# oshi-fuse-board-mk-1_1-mini-ato.net
KiCad netlist of a schematic drawn in EAGLE
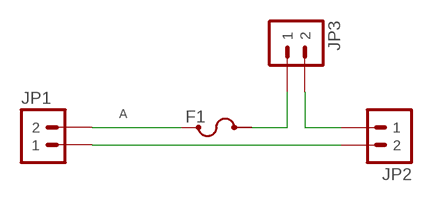
[diagram p0: schematic, sheet 1]

(export (version "E")
  (design (tool "Eeschema 10.0.6"))
  (components
    (comp (ref "F1")
      (value "FUSEMINI-AUTO")
      (footprint "eagle-import:KEYSTONE-MINI-AUTO-FUSE-HOLDER")
      (libsource (lib "eagle-import") (part "FUSEMINI-AUTO"))
    )
    (comp (ref "JP1")
      (value "M025MM")
      (footprint "eagle-import:SCREWTERMINAL-5MM-2")
      (libsource (lib "eagle-import") (part "M025MM"))
    )
    (comp (ref "JP2")
      (value "M025MM")
      (footprint "eagle-import:SCREWTERMINAL-5MM-2")
      (libsource (lib "eagle-import") (part "M025MM"))
    )
    (comp (ref "JP3")
      (value "M025MM")
      (footprint "eagle-import:SCREWTERMINAL-5MM-2")
      (libsource (lib "eagle-import") (part "M025MM"))
    )
  )
  (nets
    (net (code "1") (name "/A") (class "Default")
      (node (ref "F1") (pin "P1@1") (pinfunction "1_P1@1") (pintype "passive"))
      (node (ref "F1") (pin "P1@2") (pinfunction "1_P1@2") (pintype "passive"))
      (node (ref "JP1") (pin "2") (pinfunction "2_2") (pintype "passive"))
    )
    (net (code "2") (name "Net-(F1-2-PadP2@1)") (class "Default")
      (node (ref "F1") (pin "P2@1") (pinfunction "2_P2@1") (pintype "passive"))
      (node (ref "F1") (pin "P2@2") (pinfunction "2_P2@2") (pintype "passive"))
      (node (ref "JP3") (pin "1") (pinfunction "1_1") (pintype "passive"))
    )
    (net (code "3") (name "Net-(JP1-Pad1)") (class "Default")
      (node (ref "JP1") (pin "1") (pinfunction "1_1") (pintype "passive"))
      (node (ref "JP2") (pin "2") (pinfunction "2_2") (pintype "passive"))
    )
    (net (code "4") (name "Net-(JP2-Pad1)") (class "Default")
      (node (ref "JP2") (pin "1") (pinfunction "1_1") (pintype "passive"))
      (node (ref "JP3") (pin "2") (pinfunction "2_2") (pintype "passive"))
    )
  )
)
